# CAN.net
KiCad netlist of a schematic drawn in Altium Designer
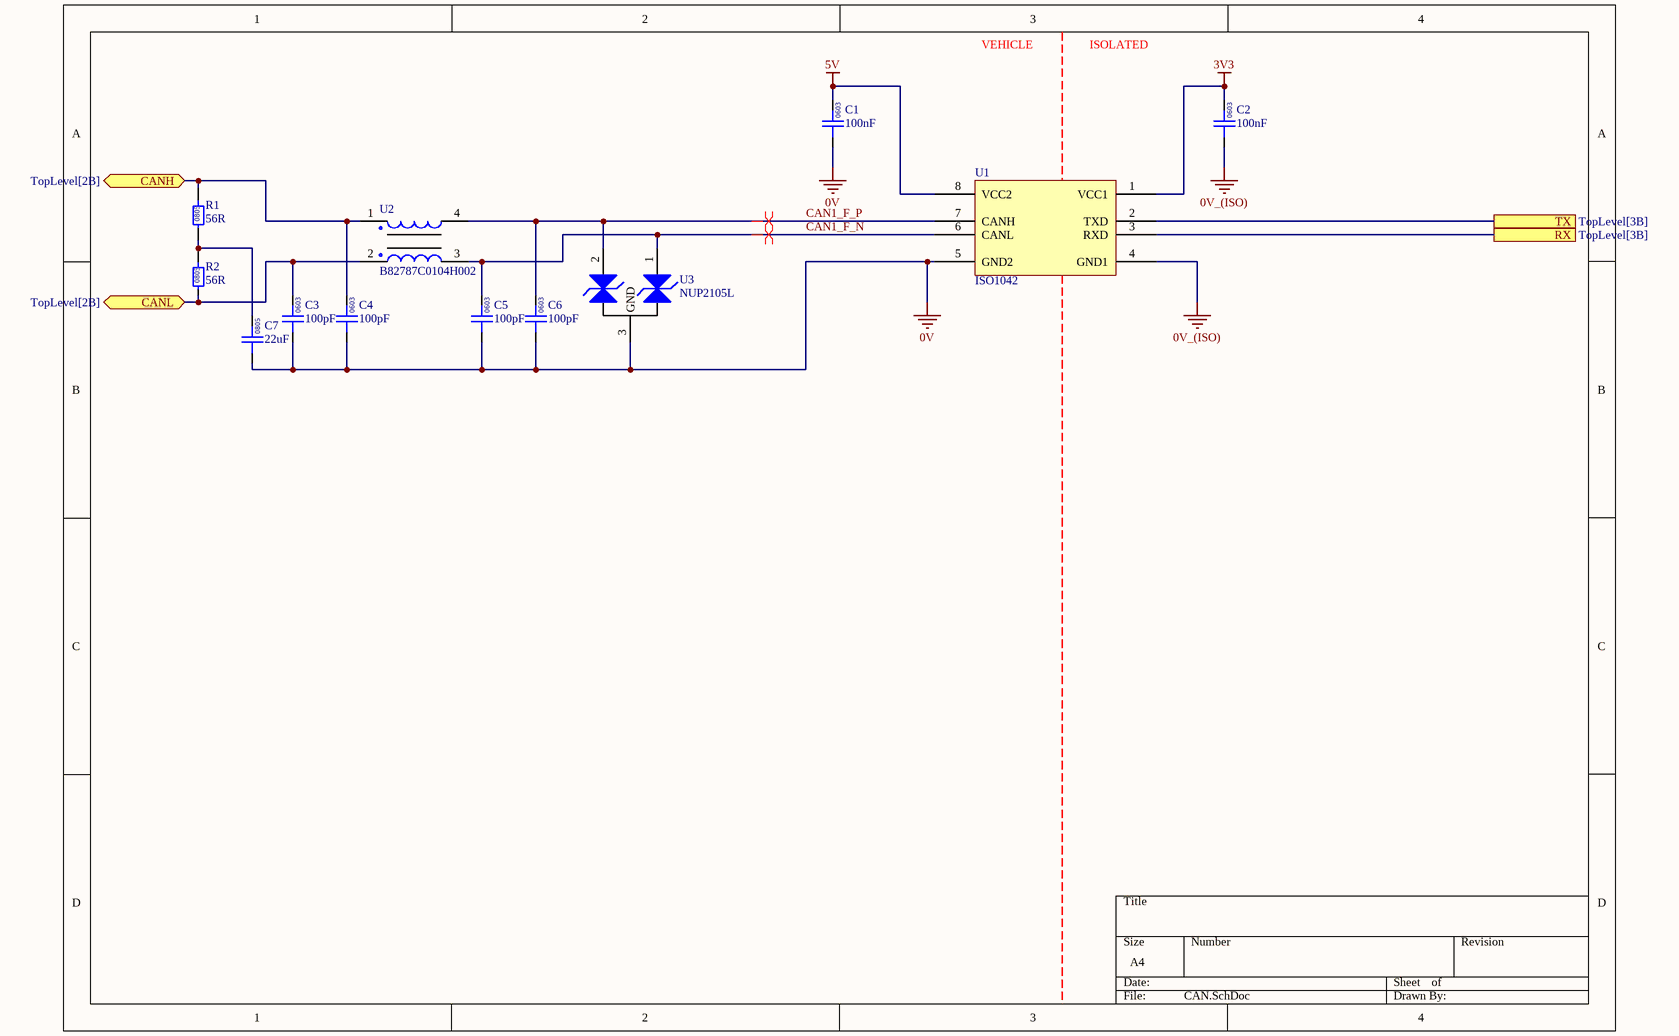
[diagram p0: CAN.SchDoc]

(export (version "E")
  (design (tool "Eeschema 10.0.6"))
  (components
    (comp (ref "C1")
      (value "100nF")
      (footprint "0603")
      (fields
        (field (name "PART NUMBER") "GCM188L81H104KA57D")
        (field (name "MANUFACTURER") "muRata")
        (field (name "TOLERANCE") "±10%")
      )
      (libsource (lib "ts_standard_library") (part "Capacitor 0603"))
    )
    (comp (ref "C2")
      (value "100nF")
      (footprint "0603")
      (fields
        (field (name "PART NUMBER") "GCM188L81H104KA57D")
        (field (name "MANUFACTURER") "muRata")
        (field (name "TOLERANCE") "±10%")
      )
      (libsource (lib "ts_standard_library") (part "Capacitor 0603"))
    )
    (comp (ref "C3")
      (value "100pF")
      (footprint "0603")
      (fields
        (field (name "PART NUMBER") "GRM1885C1H101JA01D")
        (field (name "MANUFACTURER") "Murata Electronics")
        (field (name "TOLERANCE") "±5%")
      )
      (libsource (lib "ts_standard_library") (part "Capacitor 0603"))
    )
    (comp (ref "C4")
      (value "100pF")
      (footprint "0603")
      (fields
        (field (name "PART NUMBER") "GRM1885C1H101JA01D")
        (field (name "MANUFACTURER") "Murata Electronics")
        (field (name "TOLERANCE") "±5%")
      )
      (libsource (lib "ts_standard_library") (part "Capacitor 0603"))
    )
    (comp (ref "C5")
      (value "100pF")
      (footprint "0603")
      (fields
        (field (name "PART NUMBER") "GRM1885C1H101JA01D")
        (field (name "MANUFACTURER") "Murata Electronics")
        (field (name "TOLERANCE") "±5%")
      )
      (libsource (lib "ts_standard_library") (part "Capacitor 0603"))
    )
    (comp (ref "C6")
      (value "100pF")
      (footprint "0603")
      (fields
        (field (name "PART NUMBER") "GRM1885C1H101JA01D")
        (field (name "MANUFACTURER") "Murata Electronics")
        (field (name "TOLERANCE") "±5%")
      )
      (libsource (lib "ts_standard_library") (part "Capacitor 0603"))
    )
    (comp (ref "C7")
      (value "22uF")
      (footprint "0805")
      (fields
        (field (name "PART NUMBER") "GRM21BR61A226ME51L")
        (field (name "MANUFACTURER") "muRata")
        (field (name "TOLERANCE") "20%")
      )
      (libsource (lib "ts_standard_library") (part "Capacitor 0805"))
    )
    (comp (ref "R1")
      (value "56R")
      (footprint "0805")
      (fields
        (field (name "PART NUMBER") "RC0805FR0756RL")
        (field (name "MANUFACTURER") "YAGEO")
        (field (name "TOLERANCE") "0.01")
      )
      (libsource (lib "ts_standard_library") (part "Resistor 0805"))
    )
    (comp (ref "R2")
      (value "56R")
      (footprint "0805")
      (fields
        (field (name "PART NUMBER") "RC0805FR0756RL")
        (field (name "MANUFACTURER") "YAGEO")
        (field (name "TOLERANCE") "0.01")
      )
      (libsource (lib "ts_standard_library") (part "Resistor 0805"))
    )
    (comp (ref "U1")
      (value "ISO1042")
      (footprint "TI-SOIC-8")
      (description "IC CAN TRANSCEIVER 1/1 8SOIC")
      (fields
        (field (name "MANUFACTURER") "Texas Instruments")
        (field (name "DIGIKEY PART NUMBER") "296-ISO1042BQDWVQ1-ND")
      )
      (libsource (lib "ts_standard_library") (part "ISO1042"))
    )
    (comp (ref "U2")
      (value "B82787C0104H002")
      (footprint "TDK 4-PC Pad")
      (fields
        (field (name "MANUFACTURER") "EPCOS (TDK)")
        (field (name "DIGIKEY PART NUMBER") "495-4598-1-ND")
      )
      (libsource (lib "ts_standard_library") (part "B82787C0104H002"))
    )
    (comp (ref "U3")
      (value "NUP2105L")
      (footprint "ON SOT-23")
      (description "Dual Line CAN Bus Protector")
      (fields
        (field (name "MANUFACTURER") "ON Semiconductor")
        (field (name "DIGIKEY PART NUMBER") "NUP2105LT1GOSCT-ND")
      )
      (libsource (lib "ts_standard_library") (part "NUP2105L"))
    )
  )
  (nets
    (net (code "1") (name "/CAN1_F_N") (class "Default")
      (node (ref "C5") (pin "2") (pinfunction "2_2") (pintype "passive"))
      (node (ref "U1") (pin "6") (pinfunction "CANL_6") (pintype "passive"))
      (node (ref "U2") (pin "3") (pinfunction "3_3") (pintype "passive"))
      (node (ref "U3") (pin "1") (pinfunction "CAN_H_1") (pintype "passive"))
    )
    (net (code "2") (name "/CAN1_F_P") (class "Default")
      (node (ref "C6") (pin "2") (pinfunction "2_2") (pintype "passive"))
      (node (ref "U1") (pin "7") (pinfunction "CANH_7") (pintype "passive"))
      (node (ref "U2") (pin "4") (pinfunction "4_4") (pintype "passive"))
      (node (ref "U3") (pin "2") (pinfunction "CAN_L_2") (pintype "passive"))
    )
    (net (code "3") (name "/CANH") (class "Default")
      (node (ref "C4") (pin "2") (pinfunction "2_2") (pintype "passive"))
      (node (ref "R1") (pin "2") (pinfunction "2_2") (pintype "passive"))
      (node (ref "U2") (pin "1") (pinfunction "1_1") (pintype "passive"))
    )
    (net (code "4") (name "/CANL") (class "Default")
      (node (ref "C3") (pin "2") (pinfunction "2_2") (pintype "passive"))
      (node (ref "R2") (pin "1") (pinfunction "1_1") (pintype "passive"))
      (node (ref "U2") (pin "2") (pinfunction "2_2") (pintype "passive"))
    )
    (net (code "5") (name "/RX") (class "Default")
      (node (ref "U1") (pin "3") (pinfunction "RXD_3") (pintype "passive"))
    )
    (net (code "6") (name "/TX") (class "Default")
      (node (ref "U1") (pin "2") (pinfunction "TXD_2") (pintype "passive"))
    )
    (net (code "7") (name "0V") (class "Default")
      (node (ref "C1") (pin "1") (pinfunction "1_1") (pintype "passive"))
      (node (ref "C3") (pin "1") (pinfunction "1_1") (pintype "passive"))
      (node (ref "C4") (pin "1") (pinfunction "1_1") (pintype "passive"))
      (node (ref "C5") (pin "1") (pinfunction "1_1") (pintype "passive"))
      (node (ref "C6") (pin "1") (pinfunction "1_1") (pintype "passive"))
      (node (ref "C7") (pin "1") (pinfunction "1_1") (pintype "passive"))
      (node (ref "U1") (pin "5") (pinfunction "GND2_5") (pintype "passive"))
      (node (ref "U3") (pin "3") (pinfunction "GND_3") (pintype "passive"))
    )
    (net (code "8") (name "0V_(ISO)") (class "Default")
      (node (ref "C2") (pin "1") (pinfunction "1_1") (pintype "passive"))
      (node (ref "U1") (pin "4") (pinfunction "GND1_4") (pintype "passive"))
    )
    (net (code "9") (name "3V3") (class "Default")
      (node (ref "C2") (pin "2") (pinfunction "2_2") (pintype "passive"))
      (node (ref "U1") (pin "1") (pinfunction "VCC1_1") (pintype "passive"))
    )
    (net (code "10") (name "5V") (class "Default")
      (node (ref "C1") (pin "2") (pinfunction "2_2") (pintype "passive"))
      (node (ref "U1") (pin "8") (pinfunction "VCC2_8") (pintype "passive"))
    )
    (net (code "11") (name "Net-(C7-Pad2)") (class "Default")
      (node (ref "C7") (pin "2") (pinfunction "2_2") (pintype "passive"))
      (node (ref "R1") (pin "1") (pinfunction "1_1") (pintype "passive"))
      (node (ref "R2") (pin "2") (pinfunction "2_2") (pintype "passive"))
    )
  )
)
